# Sheet8.net
KiCad netlist of a schematic drawn in Altium Designer
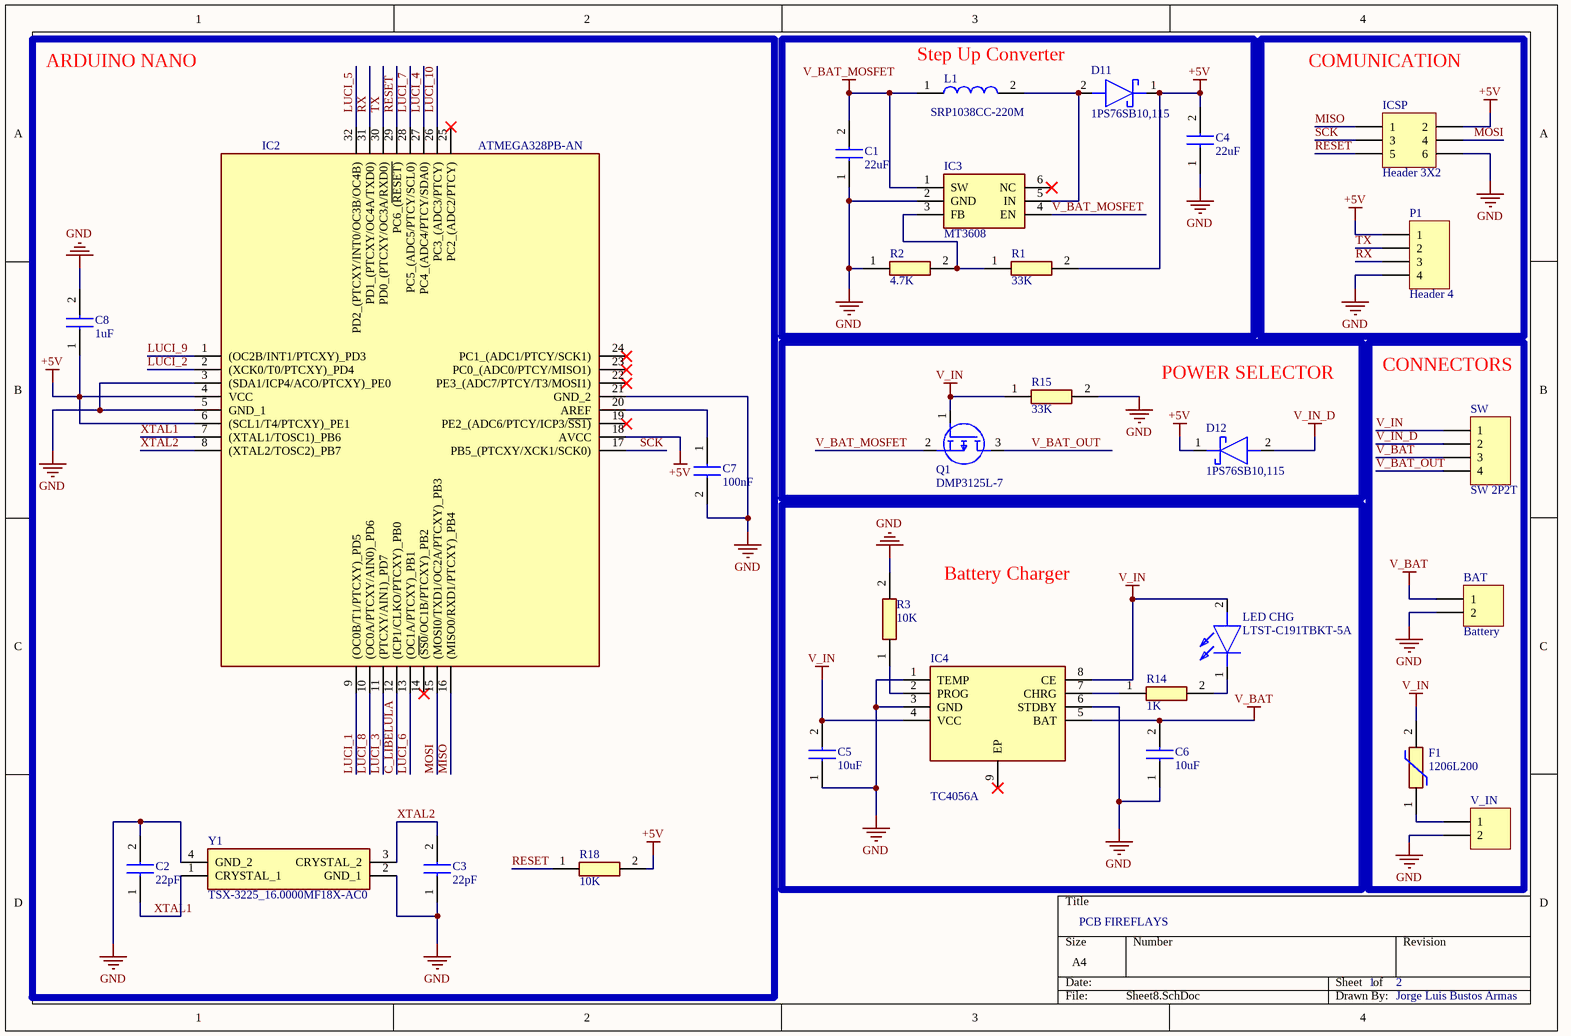
[diagram p0: Sheet8.SchDoc]

(export (version "E")
  (design (tool "Eeschema 10.0.6"))
  (components
    (comp (ref "BAT")
      (value "Battery")
      (footprint "HDR1X2")
      (description "Li-Po battery 400 mAh")
      (fields (field (name "PUBLISHER") "Altium Limited"))
      (libsource (lib "Miscellaneous Connectors") (part "Header 2"))
    )
    (comp (ref "C1")
      (value "22uF")
      (footprint "SamacSys:CAPC1608X90N")
      (description "Capacitor")
      (fields
        (field (name "MANUFACTURER_PART_NUMBER") "06035C105KAT2A")
        (field (name "MOUSER PART NUMBER") "581-06035C105KAT2A")
      )
      (libsource (lib "*") (part "06035C105KAT2A"))
    )
    (comp (ref "C2")
      (value "22pF")
      (footprint "SamacSys:CAPC1608X90N")
      (description "Capacitor")
      (fields
        (field (name "MANUFACTURER_PART_NUMBER") "06035C105KAT2A")
        (field (name "MOUSER PART NUMBER") "581-06035C105KAT2A")
      )
      (libsource (lib "*") (part "06035C105KAT2A"))
    )
    (comp (ref "C3")
      (value "22pF")
      (footprint "SamacSys:CAPC1608X90N")
      (description "Capacitor")
      (fields
        (field (name "MANUFACTURER_PART_NUMBER") "06035C105KAT2A")
        (field (name "MOUSER PART NUMBER") "581-06035C105KAT2A")
      )
      (libsource (lib "*") (part "06035C105KAT2A"))
    )
    (comp (ref "C4")
      (value "22uF")
      (footprint "SamacSys:CAPC1608X90N")
      (description "Capacitor")
      (fields
        (field (name "MANUFACTURER_PART_NUMBER") "06035C105KAT2A")
        (field (name "MOUSER PART NUMBER") "581-06035C105KAT2A")
      )
      (libsource (lib "*") (part "06035C105KAT2A"))
    )
    (comp (ref "C5")
      (value "10uF")
      (footprint "SamacSys:CAPC1608X90N")
      (description "Capacitor")
      (fields
        (field (name "MANUFACTURER_PART_NUMBER") "06035C105KAT2A")
        (field (name "MOUSER PART NUMBER") "581-06035C105KAT2A")
      )
      (libsource (lib "*") (part "06035C105KAT2A"))
    )
    (comp (ref "C6")
      (value "10uF")
      (footprint "SamacSys:CAPC1608X90N")
      (description "Capacitor")
      (fields
        (field (name "MANUFACTURER_PART_NUMBER") "06035C105KAT2A")
        (field (name "MOUSER PART NUMBER") "581-06035C105KAT2A")
      )
      (libsource (lib "*") (part "06035C105KAT2A"))
    )
    (comp (ref "C7")
      (value "100nF")
      (footprint "SamacSys:CAPC1608X90N")
      (description "Capacitor")
      (fields
        (field (name "MANUFACTURER_PART_NUMBER") "06035C105KAT2A")
        (field (name "MOUSER PART NUMBER") "581-06035C105KAT2A")
      )
      (libsource (lib "*") (part "06035C105KAT2A"))
    )
    (comp (ref "C8")
      (value "1uF")
      (footprint "SamacSys:CAPC1608X90N")
      (description "Capacitor")
      (fields
        (field (name "MANUFACTURER_PART_NUMBER") "06035C105KAT2A")
        (field (name "MOUSER PART NUMBER") "581-06035C105KAT2A")
      )
      (libsource (lib "*") (part "06035C105KAT2A"))
    )
    (comp (ref "D11")
      (value "1PS76SB10,115")
      (footprint "SamacSys:SOD2512X110N")
      (description "Schottky Diode")
      (fields (field (name "MOUSER PART NUMBER") "771-1PS76SB10-T/R"))
      (libsource (lib "SamacSys") (part "1PS76SB10,115"))
    )
    (comp (ref "D12")
      (value "1PS76SB10,115")
      (footprint "SamacSys:SOD2512X110N")
      (description "Schottky Diode")
      (fields (field (name "MOUSER PART NUMBER") "771-1PS76SB10-T/R"))
      (libsource (lib "SamacSys") (part "1PS76SB10,115"))
    )
    (comp (ref "F1")
      (value "1206L200")
      (footprint "SamacSys:1206L05015YR")
      (description "Resettable Fuse")
      (libsource (lib "SamacSys") (part "1206L200"))
    )
    (comp (ref "IC2")
      (value "ATMEGA328PB-AN")
      (footprint "SamacSys:QFP80P900X900X120-32N")
      (description "Integrated Circuit")
      (fields (field (name "MOUSER PART NUMBER") "556-ATMEGA328PB-AN"))
      (libsource (lib "*") (part "ATMEGA328PB-AN"))
    )
    (comp (ref "IC3")
      (value "MT3608")
      (footprint "SamacSys:SOT95P280X145-6N")
      (description "Integrated Circuit")
      (libsource (lib "*") (part "MT3608"))
    )
    (comp (ref "IC4")
      (value "TC4056A")
      (footprint "SamacSys:SOIC127P600X175-9N")
      (description "Integrated Circuit")
      (libsource (lib "SamacSys") (part "TC4056A"))
    )
    (comp (ref "ICSP")
      (value "Header 3X2")
      (footprint "HDR2X3")
      (description "Header, 3-Pin, Dual row")
      (fields (field (name "PUBLISHER") "Altium Limited"))
      (libsource (lib "Miscellaneous Connectors") (part "Header 3X2"))
    )
    (comp (ref "L1")
      (value "SRP1038CC-220M")
      (footprint "SamacSys:INDPM110100X400N")
      (description "Inductor")
      (fields (field (name "MOUSER PART NUMBER") "652-SRP1038CC-220M"))
      (libsource (lib "*") (part "SRP1038CC-220M"))
    )
    (comp (ref "LED CHG")
      (value "LTST-C191TBKT-5A")
      (footprint "LEDC1608X60N")
      (description "LED")
      (fields (field (name "MOUSER PART NUMBER") "859-LTST-C191TBKT-5A"))
      (libsource (lib "SamacSys") (part "LTST-C191TBKT-5A"))
    )
    (comp (ref "P1")
      (value "Header 4")
      (footprint "HDR1X4")
      (description "Header, 4-Pin")
      (fields (field (name "PUBLISHER") "Altium Limited"))
      (libsource (lib "Miscellaneous Connectors") (part "Header 4"))
    )
    (comp (ref "Q1")
      (value "DMP3125L-7")
      (footprint "SamacSys:SOT96P240X110-3N")
      (description "MOSFET (P-Channel)")
      (fields (field (name "MOUSER PART NUMBER") "621-DMP3125L-7"))
      (libsource (lib "SamacSys") (part "DMP3125L-7"))
    )
    (comp (ref "R1")
      (value "33K")
      (footprint "SamacSys:RESC1608X55N")
      (description "Resistor")
      (fields
        (field (name "MANUFACTURER_PART_NUMBER") "KTR03EZPF1501")
        (field (name "MOUSER PART NUMBER") "755-KTR03EZPF1501")
      )
      (libsource (lib "") (part "KTR03EZPF1501_1"))
    )
    (comp (ref "R2")
      (value "4.7K")
      (footprint "SamacSys:RESC1608X55N")
      (description "Resistor")
      (fields
        (field (name "MANUFACTURER_PART_NUMBER") "KTR03EZPF1501")
        (field (name "MOUSER PART NUMBER") "755-KTR03EZPF1501")
      )
      (libsource (lib "") (part "KTR03EZPF1501_1"))
    )
    (comp (ref "R3")
      (value "10K")
      (footprint "SamacSys:RESC1608X55N")
      (description "Resistor")
      (fields
        (field (name "MANUFACTURER_PART_NUMBER") "KTR03EZPF1501")
        (field (name "MOUSER PART NUMBER") "755-KTR03EZPF1501")
      )
      (libsource (lib "SamacSys") (part "KTR03EZPF1501"))
    )
    (comp (ref "R14")
      (value "1K")
      (footprint "SamacSys:RESC1608X55N")
      (description "Resistor")
      (fields
        (field (name "MANUFACTURER_PART_NUMBER") "KTR03EZPF1501")
        (field (name "MOUSER PART NUMBER") "755-KTR03EZPF1501")
      )
      (libsource (lib "") (part "KTR03EZPF1501_1"))
    )
    (comp (ref "R15")
      (value "33K")
      (footprint "SamacSys:RESC1608X55N")
      (description "Resistor")
      (fields
        (field (name "MANUFACTURER_PART_NUMBER") "KTR03EZPF1501")
        (field (name "MOUSER PART NUMBER") "755-KTR03EZPF1501")
      )
      (libsource (lib "") (part "KTR03EZPF1501_1"))
    )
    (comp (ref "R18")
      (value "10K")
      (footprint "SamacSys:RESC1608X55N")
      (description "Resistor")
      (fields
        (field (name "MANUFACTURER_PART_NUMBER") "KTR03EZPF1501")
        (field (name "MOUSER PART NUMBER") "755-KTR03EZPF1501")
      )
      (libsource (lib "") (part "KTR03EZPF1501_1"))
    )
    (comp (ref "SW")
      (value "SW 2P2T")
      (footprint "HDR1X4")
      (description "SWITCH, 2 POLES 2 THROWS")
      (fields (field (name "PUBLISHER") "Altium Limited"))
      (libsource (lib "Miscellaneous Connectors") (part "Header 4"))
    )
    (comp (ref "V_IN")
      (value "Type C female connector")
      (footprint "HDR1X2")
      (fields (field (name "PUBLISHER") "Altium Limited"))
      (libsource (lib "Miscellaneous Connectors") (part "Header 2"))
    )
    (comp (ref "Y1")
      (value "TSX-3225_16.0000MF18X-AC0")
      (footprint "SamacSys:TSX3225160000MF18XAC0")
      (description "Crystal or Oscillator")
      (fields
        (field (name "MANUFACTURER_PART_NUMBER") "TSX-3225 16.0000MF18X-AC0")
        (field (name "MOUSER PART NUMBER") "732-322516F18XAC0")
      )
      (libsource (lib "*") (part "TSX-3225_16.0000MF18X-AC0"))
    )
  )
  (nets
    (net (code "1") (name "+5V") (class "Default")
      (node (ref "C4") (pin "2") (pinfunction "2_2") (pintype "passive"))
      (node (ref "C8") (pin "1") (pinfunction "1_1") (pintype "passive"))
      (node (ref "D11") (pin "1") (pinfunction "K_1") (pintype "passive"))
      (node (ref "D12") (pin "1") (pinfunction "K_1") (pintype "passive"))
      (node (ref "IC2") (pin "18") (pinfunction "AVCC_18") (pintype "passive"))
      (node (ref "IC2") (pin "4") (pinfunction "VCC_4") (pintype "passive"))
      (node (ref "IC2") (pin "6") (pinfunction "(SCL1/T4/PTCXY)_PE1_6") (pintype "passive"))
      (node (ref "ICSP") (pin "2") (pinfunction "2_2") (pintype "passive"))
      (node (ref "P1") (pin "1") (pinfunction "1_1") (pintype "passive"))
      (node (ref "R1") (pin "2") (pinfunction "2_2") (pintype "passive"))
      (node (ref "R18") (pin "2") (pinfunction "2_2") (pintype "passive"))
    )
    (net (code "2") (name "/C_LIBELULA") (class "Default")
      (node (ref "IC2") (pin "12") (pinfunction "(ICP1/CLKO/PTCXY)_PB0_12") (pintype "passive"))
    )
    (net (code "3") (name "/LUCI_1") (class "Default")
      (node (ref "IC2") (pin "9") (pinfunction "(OC0B/T1/PTCXY)_PD5_9") (pintype "passive"))
    )
    (net (code "4") (name "/LUCI_2") (class "Default")
      (node (ref "IC2") (pin "2") (pinfunction "(XCK0/T0/PTCXY)_PD4_2") (pintype "passive"))
    )
    (net (code "5") (name "/LUCI_3") (class "Default")
      (node (ref "IC2") (pin "11") (pinfunction "(PTCXY/AIN1)_PD7_11") (pintype "passive"))
    )
    (net (code "6") (name "/LUCI_4") (class "Default")
      (node (ref "IC2") (pin "27") (pinfunction "PC4_(ADC4/PTCY/SDA0)_27") (pintype "passive"))
    )
    (net (code "7") (name "/LUCI_5") (class "Default")
      (node (ref "IC2") (pin "32") (pinfunction "PD2_(PTCXY/INT0/OC3B/OC4B)_32") (pintype "passive"))
    )
    (net (code "8") (name "/LUCI_6") (class "Default")
      (node (ref "IC2") (pin "13") (pinfunction "(OC1A/PTCXY)_PB1_13") (pintype "passive"))
    )
    (net (code "9") (name "/LUCI_7") (class "Default")
      (node (ref "IC2") (pin "28") (pinfunction "PC5_(ADC5/PTCY/SCL0)_28") (pintype "passive"))
    )
    (net (code "10") (name "/LUCI_8") (class "Default")
      (node (ref "IC2") (pin "10") (pinfunction "(OC0A/PTCXY/AIN0)_PD6_10") (pintype "passive"))
    )
    (net (code "11") (name "/LUCI_9") (class "Default")
      (node (ref "IC2") (pin "1") (pinfunction "(OC2B/INT1/PTCXY)_PD3_1") (pintype "passive"))
    )
    (net (code "12") (name "/LUCI_10") (class "Default")
      (node (ref "IC2") (pin "26") (pinfunction "PC3_(ADC3/PTCY)_26") (pintype "passive"))
    )
    (net (code "13") (name "/MISO") (class "Default")
      (node (ref "IC2") (pin "16") (pinfunction "(MISO0/RXD1/PTCXY)_PB4_16") (pintype "passive"))
      (node (ref "ICSP") (pin "1") (pinfunction "1_1") (pintype "passive"))
    )
    (net (code "14") (name "/MOSI") (class "Default")
      (node (ref "IC2") (pin "15") (pinfunction "(MOSI0/TXD1/OC2A/PTCXY)_PB3_15") (pintype "passive"))
      (node (ref "ICSP") (pin "4") (pinfunction "4_4") (pintype "passive"))
    )
    (net (code "15") (name "/RESET") (class "Default")
      (node (ref "IC2") (pin "29") (pinfunction "PC6_(~{RESET)}_29") (pintype "passive"))
      (node (ref "ICSP") (pin "5") (pinfunction "5_5") (pintype "passive"))
      (node (ref "R18") (pin "1") (pinfunction "1_1") (pintype "passive"))
    )
    (net (code "16") (name "/RX") (class "Default")
      (node (ref "IC2") (pin "31") (pinfunction "PD1_(PTCXY/OC4A/TXD0)_31") (pintype "passive"))
      (node (ref "P1") (pin "3") (pinfunction "3_3") (pintype "passive"))
    )
    (net (code "17") (name "/SCK") (class "Default")
      (node (ref "IC2") (pin "17") (pinfunction "PB5_(PTCXY/XCK1/SCK0)_17") (pintype "passive"))
      (node (ref "ICSP") (pin "3") (pinfunction "3_3") (pintype "passive"))
    )
    (net (code "18") (name "/TX") (class "Default")
      (node (ref "IC2") (pin "30") (pinfunction "PD0_(PTCXY/OC3A/RXD0)_30") (pintype "passive"))
      (node (ref "P1") (pin "2") (pinfunction "2_2") (pintype "passive"))
    )
    (net (code "19") (name "/V_BAT_OUT") (class "Default")
      (node (ref "Q1") (pin "3") (pinfunction "D_3") (pintype "passive"))
      (node (ref "SW") (pin "4") (pinfunction "4_4") (pintype "passive"))
    )
    (net (code "20") (name "/XTAL1") (class "Default")
      (node (ref "C2") (pin "1") (pinfunction "1_1") (pintype "passive"))
      (node (ref "IC2") (pin "7") (pinfunction "(XTAL1/TOSC1)_PB6_7") (pintype "passive"))
      (node (ref "Y1") (pin "1") (pinfunction "CRYSTAL_1_1") (pintype "passive"))
    )
    (net (code "21") (name "/XTAL2") (class "Default")
      (node (ref "C3") (pin "2") (pinfunction "2_2") (pintype "passive"))
      (node (ref "IC2") (pin "8") (pinfunction "(XTAL2/TOSC2)_PB7_8") (pintype "passive"))
      (node (ref "Y1") (pin "3") (pinfunction "CRYSTAL_2_3") (pintype "passive"))
    )
    (net (code "22") (name "GND") (class "Default")
      (node (ref "BAT") (pin "2") (pinfunction "2_2") (pintype "passive"))
      (node (ref "C1") (pin "1") (pinfunction "1_1") (pintype "passive"))
      (node (ref "C2") (pin "2") (pinfunction "2_2") (pintype "passive"))
      (node (ref "C3") (pin "1") (pinfunction "1_1") (pintype "passive"))
      (node (ref "C4") (pin "1") (pinfunction "1_1") (pintype "passive"))
      (node (ref "C5") (pin "1") (pinfunction "1_1") (pintype "passive"))
      (node (ref "C6") (pin "1") (pinfunction "1_1") (pintype "passive"))
      (node (ref "C7") (pin "2") (pinfunction "2_2") (pintype "passive"))
      (node (ref "C8") (pin "2") (pinfunction "2_2") (pintype "passive"))
      (node (ref "IC2") (pin "21") (pinfunction "GND_2_21") (pintype "passive"))
      (node (ref "IC2") (pin "3") (pinfunction "(SDA1/ICP4/ACO/PTCXY)_PE0_3") (pintype "passive"))
      (node (ref "IC2") (pin "5") (pinfunction "GND_1_5") (pintype "passive"))
      (node (ref "IC3") (pin "2") (pinfunction "GND_2") (pintype "passive"))
      (node (ref "IC4") (pin "1") (pinfunction "TEMP_1") (pintype "passive"))
      (node (ref "IC4") (pin "3") (pinfunction "GND_3") (pintype "passive"))
      (node (ref "IC4") (pin "6") (pinfunction "STDBY_6") (pintype "passive"))
      (node (ref "ICSP") (pin "6") (pinfunction "6_6") (pintype "passive"))
      (node (ref "P1") (pin "4") (pinfunction "4_4") (pintype "passive"))
      (node (ref "R15") (pin "2") (pinfunction "2_2") (pintype "passive"))
      (node (ref "R2") (pin "1") (pinfunction "1_1") (pintype "passive"))
      (node (ref "R3") (pin "2") (pinfunction "2_2") (pintype "passive"))
      (node (ref "V_IN") (pin "2") (pinfunction "2_2") (pintype "passive"))
      (node (ref "Y1") (pin "2") (pinfunction "GND_1_2") (pintype "passive"))
      (node (ref "Y1") (pin "4") (pinfunction "GND_2_4") (pintype "passive"))
    )
    (net (code "23") (name "Net-(D11-A)") (class "Default")
      (node (ref "D11") (pin "2") (pinfunction "A_2") (pintype "passive"))
      (node (ref "IC3") (pin "5") (pinfunction "IN_5") (pintype "passive"))
      (node (ref "L1") (pin "2") (pinfunction "2_2") (pintype "passive"))
    )
    (net (code "24") (name "Net-(F1-Pad1)") (class "Default")
      (node (ref "F1") (pin "1") (pinfunction "1_1") (pintype "passive"))
      (node (ref "V_IN") (pin "1") (pinfunction "1_1") (pintype "passive"))
    )
    (net (code "25") (name "Net-(IC2-AREF)") (class "Default")
      (node (ref "C7") (pin "1") (pinfunction "1_1") (pintype "passive"))
      (node (ref "IC2") (pin "20") (pinfunction "AREF_20") (pintype "passive"))
    )
    (net (code "26") (name "Net-(IC3-FB)") (class "Default")
      (node (ref "IC3") (pin "3") (pinfunction "FB_3") (pintype "passive"))
      (node (ref "R1") (pin "1") (pinfunction "1_1") (pintype "passive"))
      (node (ref "R2") (pin "2") (pinfunction "2_2") (pintype "passive"))
    )
    (net (code "27") (name "Net-(IC4-CHRG)") (class "Default")
      (node (ref "IC4") (pin "7") (pinfunction "CHRG_7") (pintype "passive"))
      (node (ref "R14") (pin "1") (pinfunction "1_1") (pintype "passive"))
    )
    (net (code "28") (name "Net-(IC4-PROG)") (class "Default")
      (node (ref "IC4") (pin "2") (pinfunction "PROG_2") (pintype "passive"))
      (node (ref "R3") (pin "1") (pinfunction "1_1") (pintype "passive"))
    )
    (net (code "29") (name "Net-(LED CHG-K)") (class "Default")
      (node (ref "LED CHG") (pin "1") (pinfunction "K_1") (pintype "passive"))
      (node (ref "R14") (pin "2") (pinfunction "2_2") (pintype "passive"))
    )
    (net (code "30") (name "V_BAT") (class "Default")
      (node (ref "BAT") (pin "1") (pinfunction "1_1") (pintype "passive"))
      (node (ref "C6") (pin "2") (pinfunction "2_2") (pintype "passive"))
      (node (ref "IC4") (pin "5") (pinfunction "BAT_5") (pintype "passive"))
      (node (ref "SW") (pin "3") (pinfunction "3_3") (pintype "passive"))
    )
    (net (code "31") (name "V_BAT_MOSFET") (class "Default")
      (node (ref "C1") (pin "2") (pinfunction "2_2") (pintype "passive"))
      (node (ref "IC3") (pin "1") (pinfunction "SW_1") (pintype "passive"))
      (node (ref "IC3") (pin "4") (pinfunction "EN_4") (pintype "passive"))
      (node (ref "L1") (pin "1") (pinfunction "1_1") (pintype "passive"))
      (node (ref "Q1") (pin "2") (pinfunction "S_2") (pintype "passive"))
    )
    (net (code "32") (name "V_IN") (class "Default")
      (node (ref "C5") (pin "2") (pinfunction "2_2") (pintype "passive"))
      (node (ref "F1") (pin "2") (pinfunction "2_2") (pintype "passive"))
      (node (ref "IC4") (pin "4") (pinfunction "VCC_4") (pintype "passive"))
      (node (ref "IC4") (pin "8") (pinfunction "CE_8") (pintype "passive"))
      (node (ref "LED CHG") (pin "2") (pinfunction "A_2") (pintype "passive"))
      (node (ref "Q1") (pin "1") (pinfunction "G_1") (pintype "passive"))
      (node (ref "R15") (pin "1") (pinfunction "1_1") (pintype "passive"))
      (node (ref "SW") (pin "1") (pinfunction "1_1") (pintype "passive"))
    )
    (net (code "33") (name "V_IN_D") (class "Default")
      (node (ref "D12") (pin "2") (pinfunction "A_2") (pintype "passive"))
      (node (ref "SW") (pin "2") (pinfunction "2_2") (pintype "passive"))
    )
    (net (code "34") (name "unconnected-(IC2-(~{SS0}{slash}OC1B{slash}PTCXY)_PB2-Pad14)") (class "Default")
      (node (ref "IC2") (pin "14") (pinfunction "(~{SS0}/OC1B/PTCXY)_PB2_14") (pintype "passive+no_connect"))
    )
    (net (code "35") (name "unconnected-(IC2-PC0_(ADC0{slash}PTCY{slash}MISO1)-Pad23)") (class "Default")
      (node (ref "IC2") (pin "23") (pinfunction "PC0_(ADC0/PTCY/MISO1)_23") (pintype "passive+no_connect"))
    )
    (net (code "36") (name "unconnected-(IC2-PC1_(ADC1{slash}PTCY{slash}SCK1)-Pad24)") (class "Default")
      (node (ref "IC2") (pin "24") (pinfunction "PC1_(ADC1/PTCY/SCK1)_24") (pintype "passive+no_connect"))
    )
    (net (code "37") (name "unconnected-(IC2-PC2_(ADC2{slash}PTCY)-Pad25)") (class "Default")
      (node (ref "IC2") (pin "25") (pinfunction "PC2_(ADC2/PTCY)_25") (pintype "passive+no_connect"))
    )
    (net (code "38") (name "unconnected-(IC2-PE2_(ADC6{slash}PTCY{slash}ICP3{slash}~{SS1)}-Pad19)") (class "Default")
      (node (ref "IC2") (pin "19") (pinfunction "PE2_(ADC6/PTCY/ICP3/~{SS1)}_19") (pintype "passive+no_connect"))
    )
    (net (code "39") (name "unconnected-(IC2-PE3_(ADC7{slash}PTCY{slash}T3{slash}MOSI1)-Pad22)") (class "Default")
      (node (ref "IC2") (pin "22") (pinfunction "PE3_(ADC7/PTCY/T3/MOSI1)_22") (pintype "passive+no_connect"))
    )
    (net (code "40") (name "unconnected-(IC3-NC-Pad6)") (class "Default")
      (node (ref "IC3") (pin "6") (pinfunction "NC_6") (pintype "passive+no_connect"))
    )
    (net (code "41") (name "unconnected-(IC4-EP-Pad9)") (class "Default")
      (node (ref "IC4") (pin "9") (pinfunction "EP_9") (pintype "passive+no_connect"))
    )
  )
)
